# mbedXdotShield-V_1_0_1.net
KiCad netlist of a schematic drawn in EAGLE
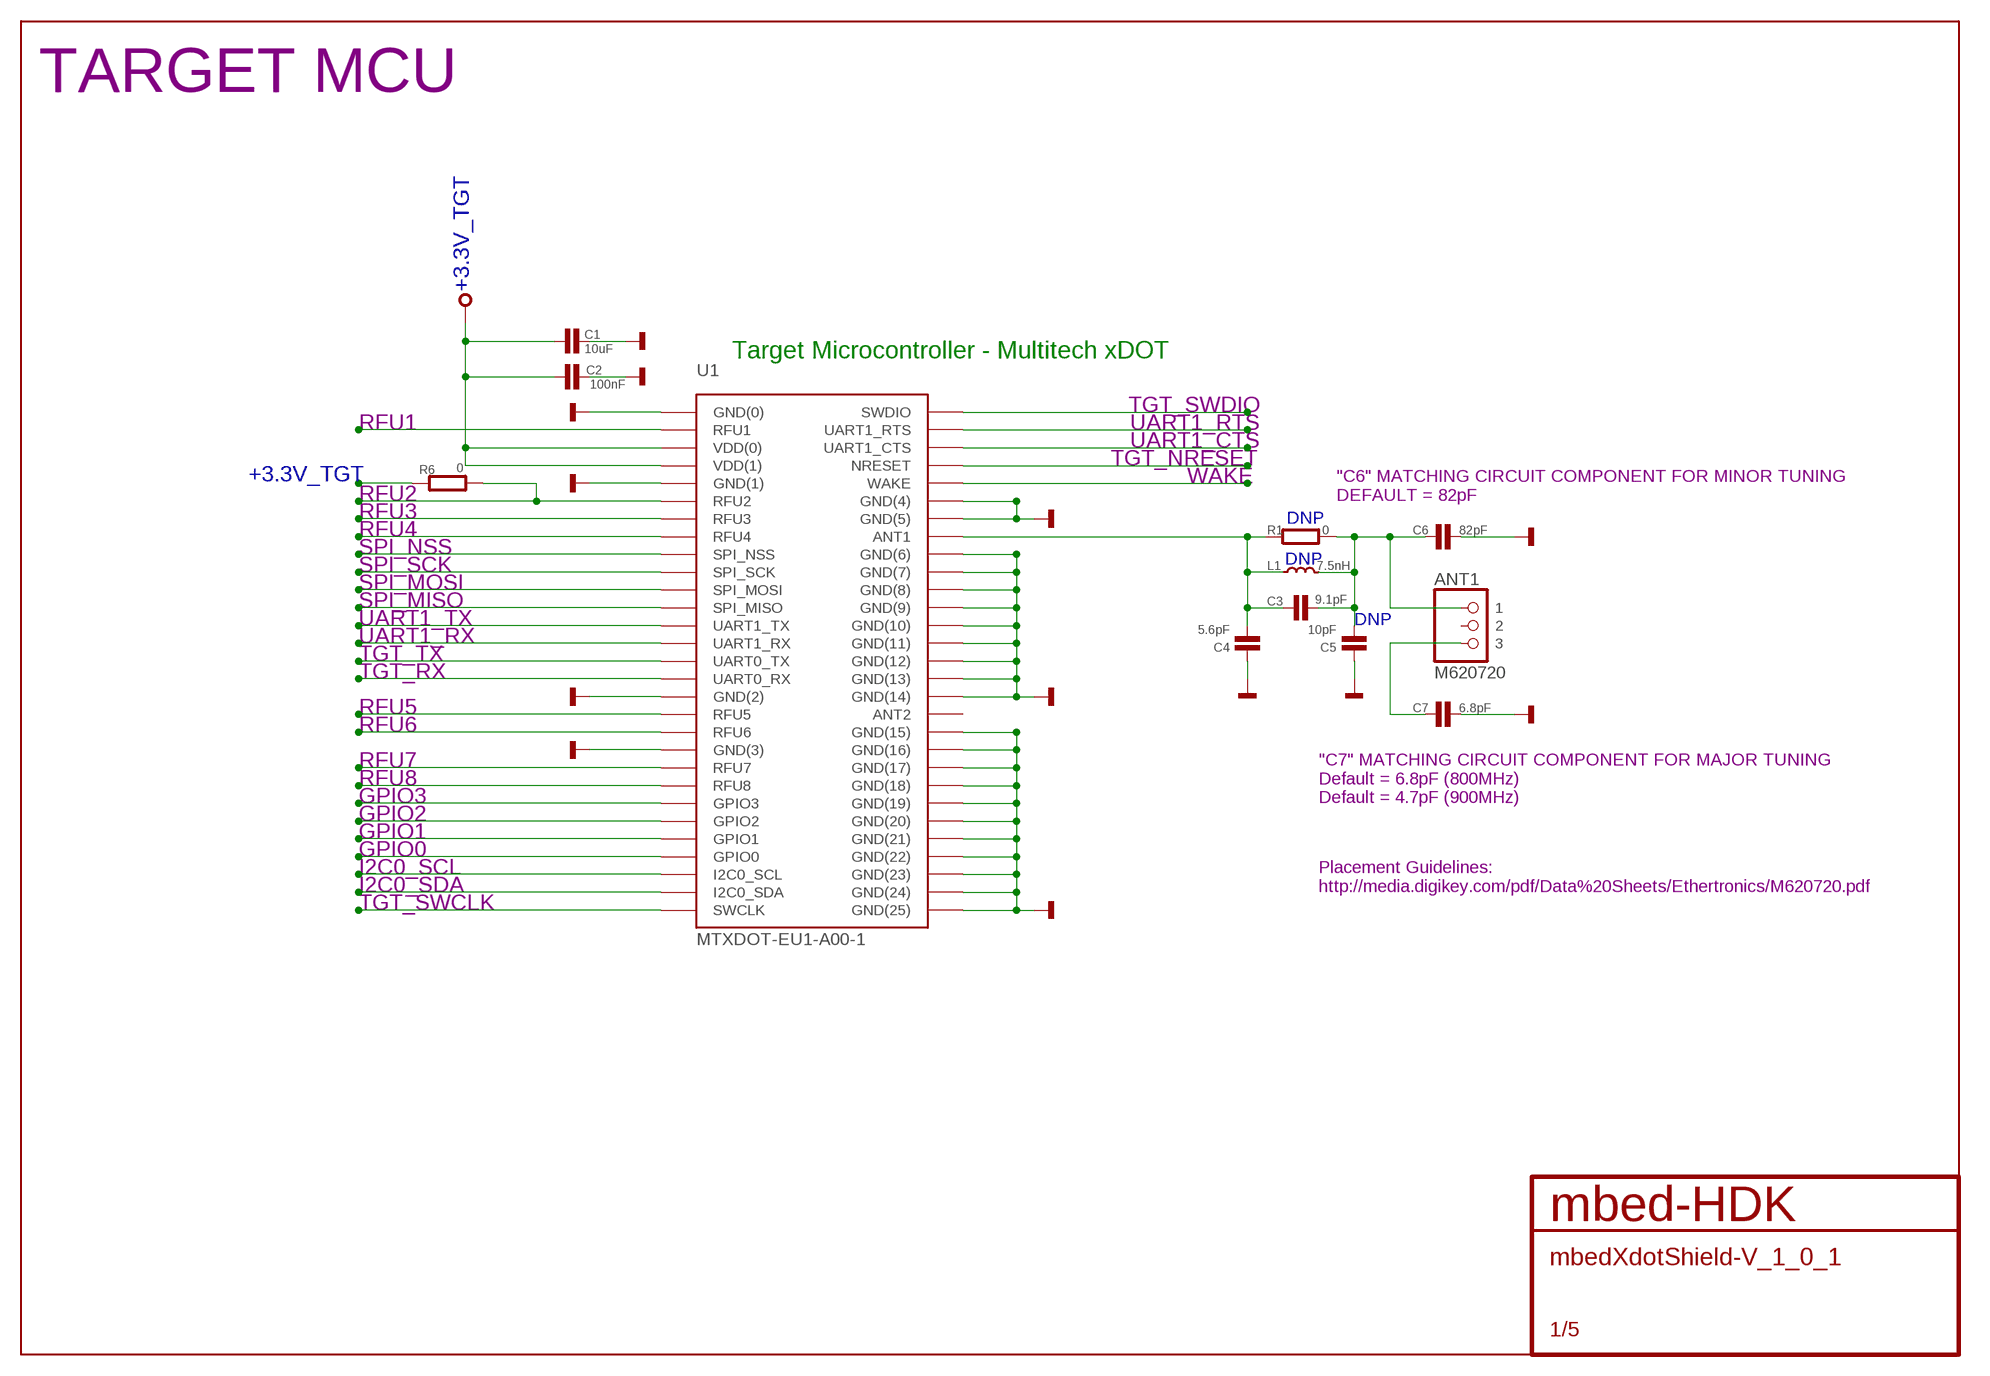
[diagram p0: schematic, sheet 1]
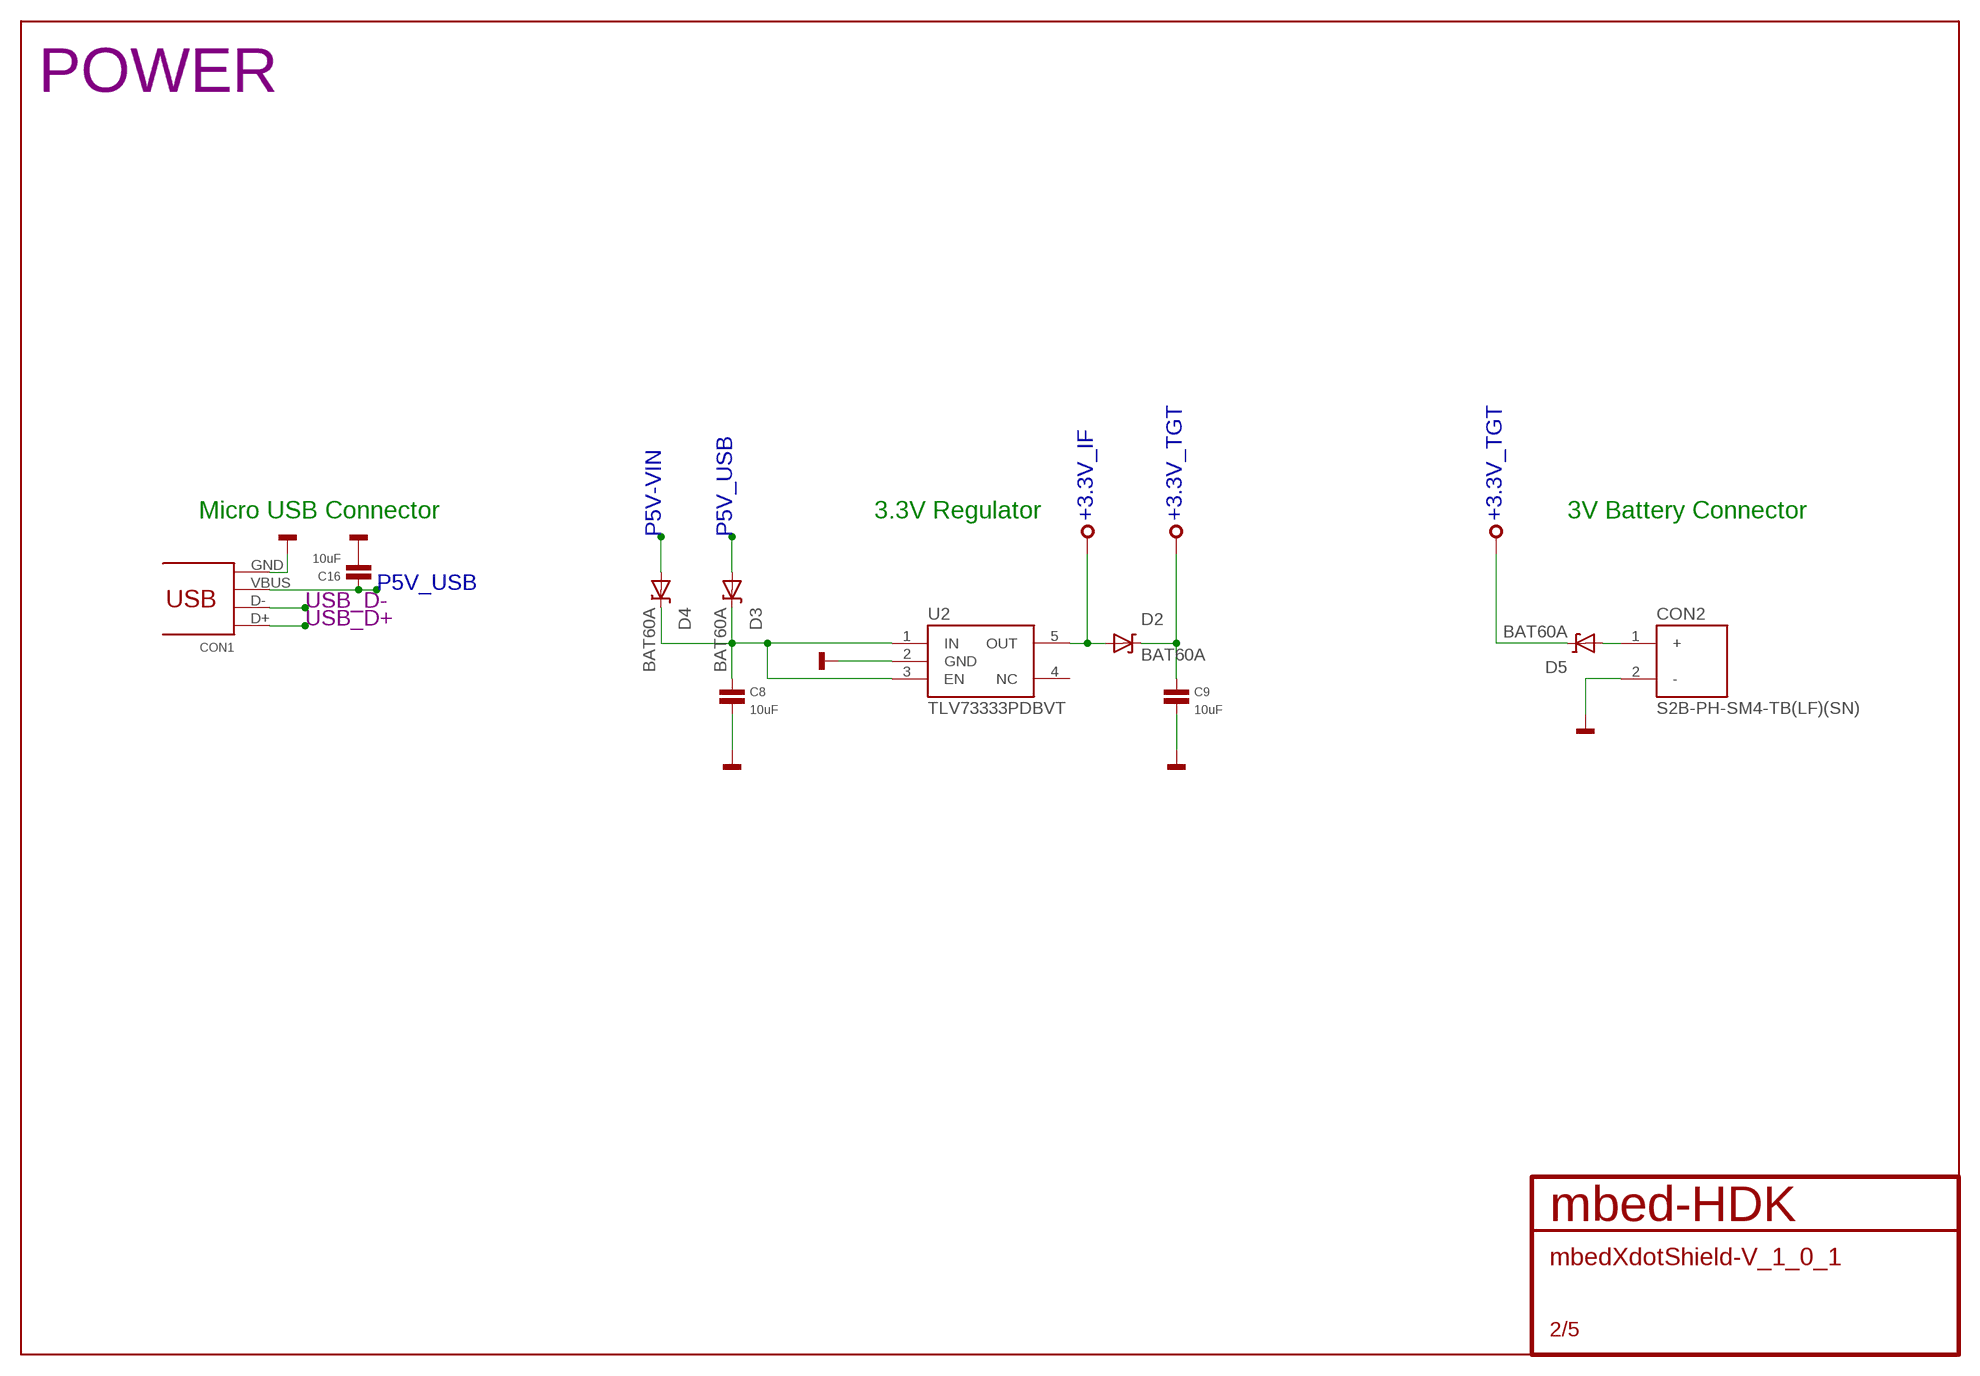
[diagram p1: schematic, sheet 2]
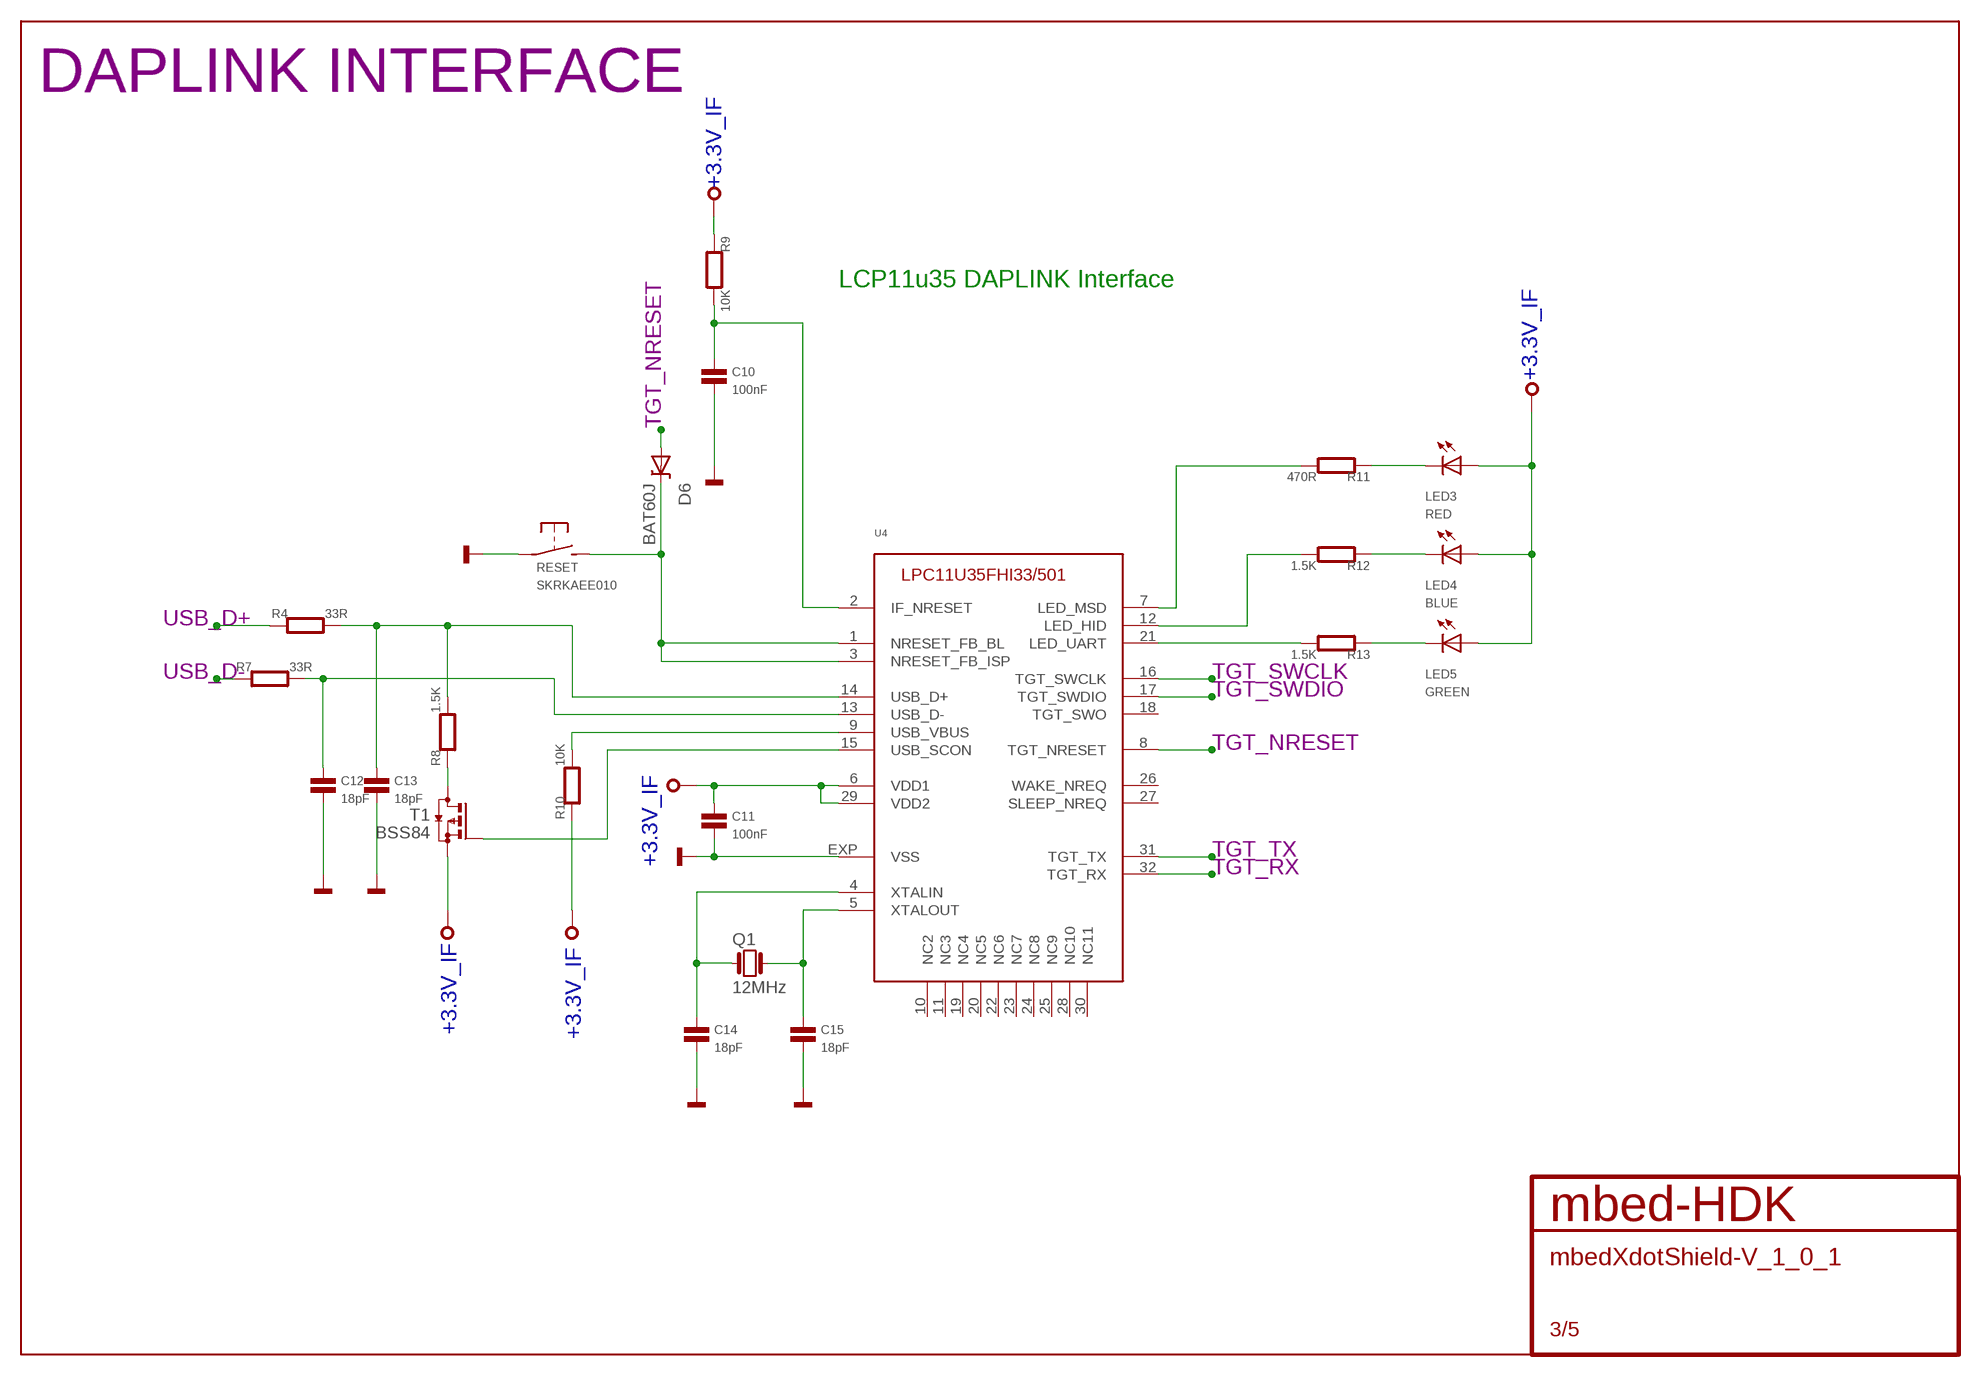
[diagram p2: schematic, sheet 3]
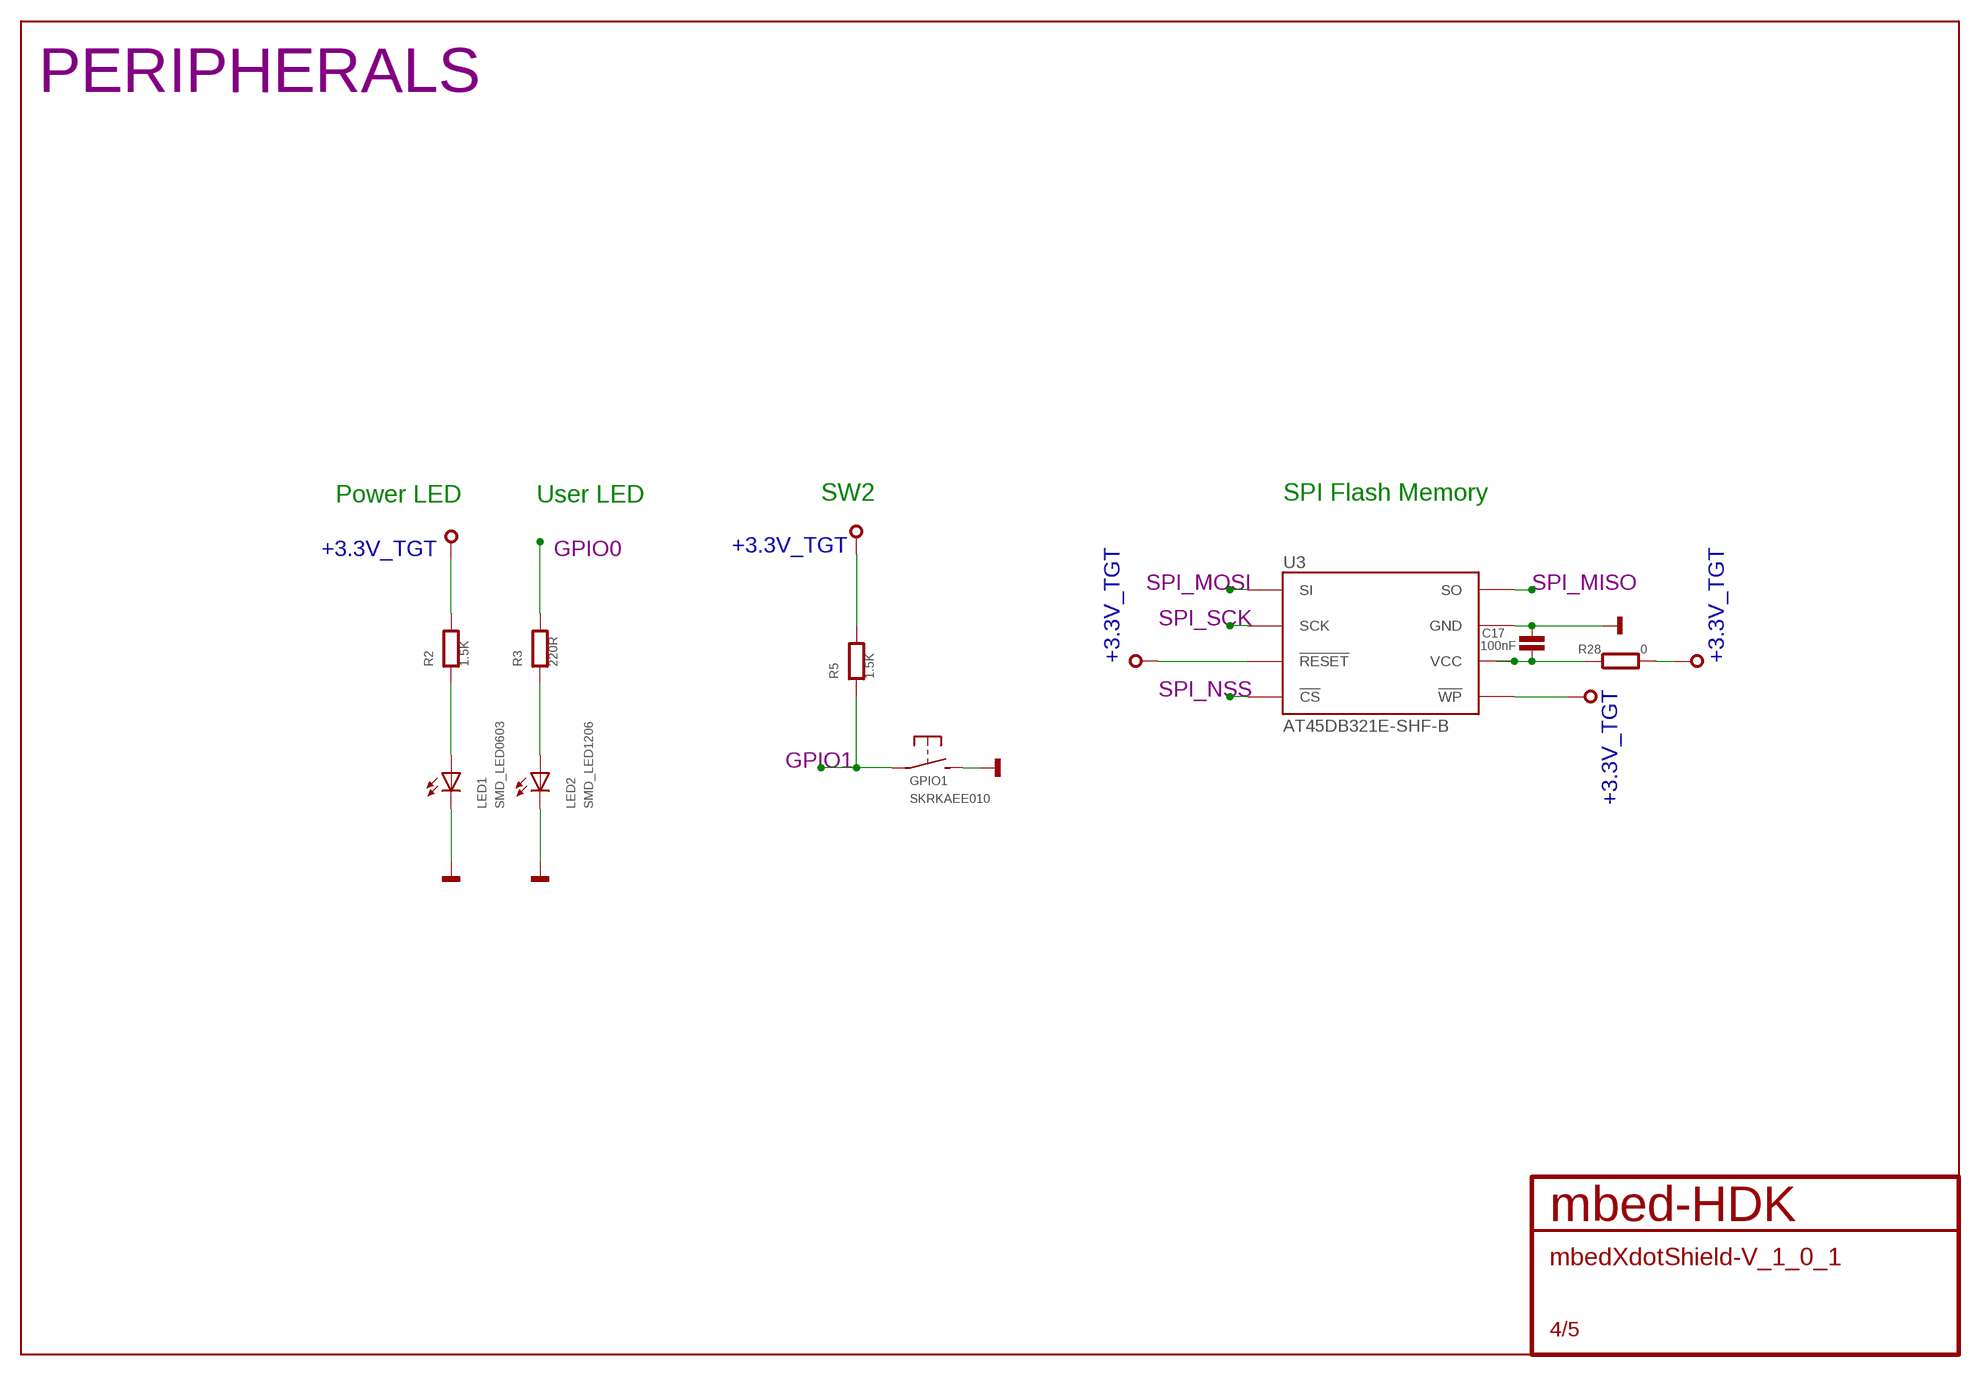
[diagram p3: schematic, sheet 4]
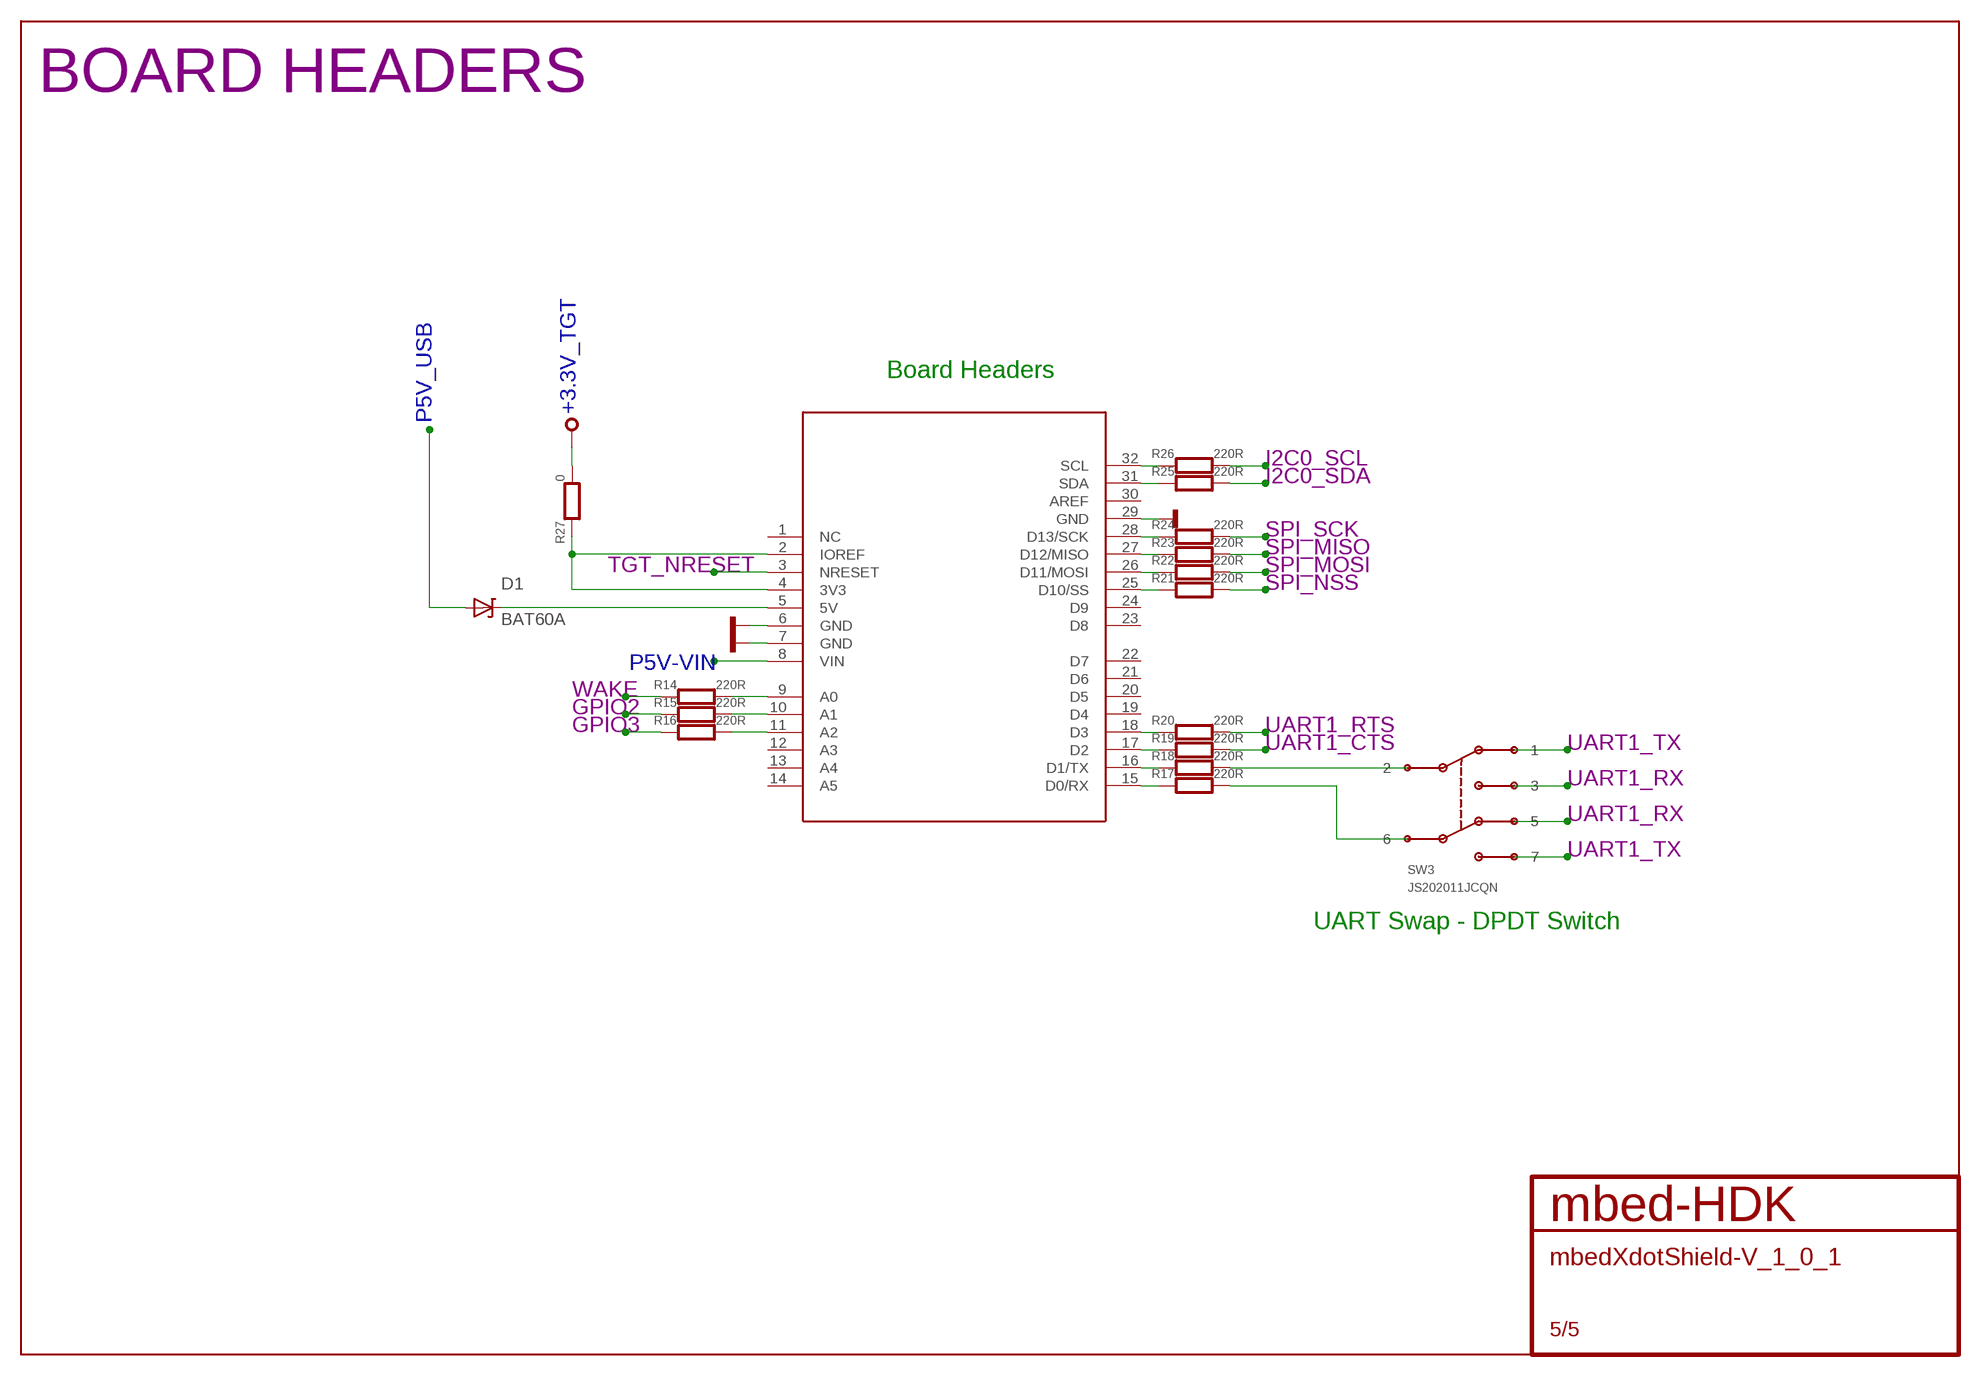
[diagram p4: schematic, sheet 5]

(export (version "E")
  (design (tool "Eeschema 10.0.6"))
  (components
    (comp (ref "C17")
      (value "100nF")
      (footprint "eagle-import:0603")
      (libsource (lib "eagle-import") (part "CAPACITOR0603"))
    )
    (comp (ref "GPIO1")
      (value "SKRKAEE010")
      (footprint "eagle-import:SKRKAEE010")
      (fields (field (name "MF") "ALPS"))
      (libsource (lib "eagle-import") (part "SKRKAEE010"))
    )
    (comp (ref "LED1")
      (value "SMD_LED0603")
      (footprint "eagle-import:CHIPLED_0603")
      (fields (field (name "MF") "Wurth Electronics Inc"))
      (libsource (lib "eagle-import") (part "SMD_LED0603"))
    )
    (comp (ref "LED2")
      (value "SMD_LED1206")
      (footprint "eagle-import:CHIPLED_1206")
      (fields (field (name "MF") "Wurth Electronics Inc"))
      (libsource (lib "eagle-import") (part "SMD_LED1206"))
    )
    (comp (ref "R2")
      (value "1.5K")
      (footprint "eagle-import:0402")
      (libsource (lib "eagle-import") (part "RESISTOR0402"))
    )
    (comp (ref "R3")
      (value "220R")
      (footprint "eagle-import:0402")
      (libsource (lib "eagle-import") (part "RESISTOR0402"))
    )
    (comp (ref "R5")
      (value "1.5K")
      (footprint "eagle-import:0402")
      (libsource (lib "eagle-import") (part "RESISTOR0402"))
    )
    (comp (ref "R28")
      (value "0")
      (footprint "eagle-import:0402")
      (libsource (lib "eagle-import") (part "RESISTOR0402"))
    )
    (comp (ref "U3")
      (value "AT45DB321E-SHF-B")
      (footprint "eagle-import:SO8")
      (fields (field (name "MF") "Adesto Technologies"))
      (libsource (lib "eagle-import") (part "AT45DB321E-SHF-B"))
    )
    (comp (ref "C10")
      (value "100nF")
      (footprint "eagle-import:0402")
      (libsource (lib "eagle-import") (part "CAPACITOR0402"))
    )
    (comp (ref "C11")
      (value "100nF")
      (footprint "eagle-import:0402")
      (libsource (lib "eagle-import") (part "CAPACITOR0402"))
    )
    (comp (ref "C12")
      (value "18pF")
      (footprint "eagle-import:0402")
      (libsource (lib "eagle-import") (part "CAPACITOR0402"))
    )
    (comp (ref "C13")
      (value "18pF")
      (footprint "eagle-import:0402")
      (libsource (lib "eagle-import") (part "CAPACITOR0402"))
    )
    (comp (ref "C14")
      (value "18pF")
      (footprint "eagle-import:0402")
      (libsource (lib "eagle-import") (part "CAPACITOR0402"))
    )
    (comp (ref "C15")
      (value "18pF")
      (footprint "eagle-import:0402")
      (libsource (lib "eagle-import") (part "CAPACITOR0402"))
    )
    (comp (ref "D6")
      (value "BAT60J")
      (footprint "eagle-import:SOD323")
      (fields (field (name "MF") "STMicroelectronics"))
      (libsource (lib "eagle-import") (part "BAT60J"))
    )
    (comp (ref "LED3")
      (value "RED")
      (footprint "eagle-import:CHIPLED_0603")
      (fields (field (name "MF") "Wurth Electronics Inc"))
      (libsource (lib "eagle-import") (part "SMD_LED0603"))
    )
    (comp (ref "LED4")
      (value "BLUE")
      (footprint "eagle-import:CHIPLED_0603")
      (fields (field (name "MF") "Wurth Electronics Inc"))
      (libsource (lib "eagle-import") (part "SMD_LED0603"))
    )
    (comp (ref "LED5")
      (value "GREEN")
      (footprint "eagle-import:CHIPLED_0603")
      (fields (field (name "MF") "Wurth Electronics Inc"))
      (libsource (lib "eagle-import") (part "SMD_LED0603"))
    )
    (comp (ref "Q1")
      (value "12MHz")
      (footprint "eagle-import:3.2X.2.5")
      (libsource (lib "eagle-import") (part "Q_3.2X2.5"))
    )
    (comp (ref "R4")
      (value "33R")
      (footprint "eagle-import:0402")
      (libsource (lib "eagle-import") (part "RESISTOR0402"))
    )
    (comp (ref "R7")
      (value "33R")
      (footprint "eagle-import:0402")
      (libsource (lib "eagle-import") (part "RESISTOR0402"))
    )
    (comp (ref "R8")
      (value "1.5K")
      (footprint "eagle-import:0402")
      (libsource (lib "eagle-import") (part "RESISTOR0402"))
    )
    (comp (ref "R9")
      (value "10K")
      (footprint "eagle-import:0402")
      (libsource (lib "eagle-import") (part "RESISTOR0402"))
    )
    (comp (ref "R10")
      (value "10K")
      (footprint "eagle-import:0402")
      (libsource (lib "eagle-import") (part "RESISTOR0402"))
    )
    (comp (ref "R11")
      (value "470R")
      (footprint "eagle-import:0402")
      (libsource (lib "eagle-import") (part "RESISTOR0402"))
    )
    (comp (ref "R12")
      (value "1.5K")
      (footprint "eagle-import:0402")
      (libsource (lib "eagle-import") (part "RESISTOR0402"))
    )
    (comp (ref "R13")
      (value "1.5K")
      (footprint "eagle-import:0402")
      (libsource (lib "eagle-import") (part "RESISTOR0402"))
    )
    (comp (ref "RESET")
      (value "SKRKAEE010")
      (footprint "eagle-import:SKRKAEE010")
      (fields (field (name "MF") "ALPS"))
      (libsource (lib "eagle-import") (part "SKRKAEE010"))
    )
    (comp (ref "T1")
      (value "BSS84")
      (footprint "eagle-import:SOT23-3")
      (fields (field (name "MF") "Fairchild Semiconductor"))
      (libsource (lib "eagle-import") (part "BSS84"))
    )
    (comp (ref "U4")
      (value "IF-LPC11U35")
      (footprint "eagle-import:HVQFN33")
      (libsource (lib "eagle-import") (part "IF-LPC11U35"))
    )
    (comp (ref "C8")
      (value "10uF")
      (footprint "eagle-import:0603")
      (libsource (lib "eagle-import") (part "CAPACITOR0603"))
    )
    (comp (ref "C9")
      (value "10uF")
      (footprint "eagle-import:0603")
      (libsource (lib "eagle-import") (part "CAPACITOR0603"))
    )
    (comp (ref "C16")
      (value "10uF")
      (footprint "eagle-import:0603")
      (libsource (lib "eagle-import") (part "CAPACITOR0603"))
    )
    (comp (ref "CON1")
      (value "47346-0001")
      (footprint "eagle-import:USB-MICRO-B-H")
      (fields (field (name "MF") "MOLEX"))
      (libsource (lib "eagle-import") (part "47346-0001"))
    )
    (comp (ref "CON2")
      (value "S2B-PH-SM4-TB(LF)(SN)")
      (footprint "eagle-import:S2B-PH-SM4-TB(LF)(SN)")
      (fields (field (name "MF") "JST"))
      (libsource (lib "eagle-import") (part "S2B-PH-SM4-TB(LF)(SN)"))
    )
    (comp (ref "D2")
      (value "BAT60A")
      (footprint "eagle-import:SOD323")
      (fields (field (name "MF") "Infineon"))
      (libsource (lib "eagle-import") (part "BAT60A"))
    )
    (comp (ref "D3")
      (value "BAT60A")
      (footprint "eagle-import:SOD323")
      (fields (field (name "MF") "Infineon"))
      (libsource (lib "eagle-import") (part "BAT60A"))
    )
    (comp (ref "D4")
      (value "BAT60A")
      (footprint "eagle-import:SOD323")
      (fields (field (name "MF") "Infineon"))
      (libsource (lib "eagle-import") (part "BAT60A"))
    )
    (comp (ref "D5")
      (value "BAT60A")
      (footprint "eagle-import:SOD323")
      (fields (field (name "MF") "Infineon"))
      (libsource (lib "eagle-import") (part "BAT60A"))
    )
    (comp (ref "U2")
      (value "TLV73333PDBVT")
      (footprint "eagle-import:SOT23-5")
      (fields (field (name "MF") "Texas Instruments"))
      (libsource (lib "eagle-import") (part "TLV73333PDBVT"))
    )
    (comp (ref "BRD1")
      (value "K64F/K22F-SHIELD")
      (footprint "eagle-import:K64F_K22F")
      (libsource (lib "eagle-import") (part "K64F/K22F-SHIELD"))
    )
    (comp (ref "D1")
      (value "BAT60A")
      (footprint "eagle-import:SOD323")
      (fields (field (name "MF") "Infineon"))
      (libsource (lib "eagle-import") (part "BAT60A"))
    )
    (comp (ref "R14")
      (value "220R")
      (footprint "eagle-import:0402")
      (libsource (lib "eagle-import") (part "RESISTOR0402"))
    )
    (comp (ref "R15")
      (value "220R")
      (footprint "eagle-import:0402")
      (libsource (lib "eagle-import") (part "RESISTOR0402"))
    )
    (comp (ref "R16")
      (value "220R")
      (footprint "eagle-import:0402")
      (libsource (lib "eagle-import") (part "RESISTOR0402"))
    )
    (comp (ref "R17")
      (value "220R")
      (footprint "eagle-import:0402")
      (libsource (lib "eagle-import") (part "RESISTOR0402"))
    )
    (comp (ref "R18")
      (value "220R")
      (footprint "eagle-import:0402")
      (libsource (lib "eagle-import") (part "RESISTOR0402"))
    )
    (comp (ref "R19")
      (value "220R")
      (footprint "eagle-import:0402")
      (libsource (lib "eagle-import") (part "RESISTOR0402"))
    )
    (comp (ref "R20")
      (value "220R")
      (footprint "eagle-import:0402")
      (libsource (lib "eagle-import") (part "RESISTOR0402"))
    )
    (comp (ref "R21")
      (value "220R")
      (footprint "eagle-import:0402")
      (libsource (lib "eagle-import") (part "RESISTOR0402"))
    )
    (comp (ref "R22")
      (value "220R")
      (footprint "eagle-import:0402")
      (libsource (lib "eagle-import") (part "RESISTOR0402"))
    )
    (comp (ref "R23")
      (value "220R")
      (footprint "eagle-import:0402")
      (libsource (lib "eagle-import") (part "RESISTOR0402"))
    )
    (comp (ref "R24")
      (value "220R")
      (footprint "eagle-import:0402")
      (libsource (lib "eagle-import") (part "RESISTOR0402"))
    )
    (comp (ref "R25")
      (value "220R")
      (footprint "eagle-import:0402")
      (libsource (lib "eagle-import") (part "RESISTOR0402"))
    )
    (comp (ref "R26")
      (value "220R")
      (footprint "eagle-import:0402")
      (libsource (lib "eagle-import") (part "RESISTOR0402"))
    )
    (comp (ref "R27")
      (value "0")
      (footprint "eagle-import:0402")
      (libsource (lib "eagle-import") (part "RESISTOR0402"))
    )
    (comp (ref "SW3")
      (value "JS202011JCQN")
      (footprint "eagle-import:JS202011JCQN")
      (fields (field (name "MF") "C&K Components"))
      (libsource (lib "eagle-import") (part "JS202011JCQN"))
    )
    (comp (ref "ANT1")
      (value "M620720")
      (footprint "eagle-import:M620720")
      (fields (field (name "MF") "Ethertronics"))
      (libsource (lib "eagle-import") (part "M620720"))
    )
    (comp (ref "C1")
      (value "10uF")
      (footprint "eagle-import:0603")
      (libsource (lib "eagle-import") (part "CAPACITOR0603"))
    )
    (comp (ref "C2")
      (value "100nF")
      (footprint "eagle-import:0603")
      (libsource (lib "eagle-import") (part "CAPACITOR0603"))
    )
    (comp (ref "C3")
      (value "9.1pF")
      (footprint "eagle-import:0402")
      (libsource (lib "eagle-import") (part "CAPACITOR0402"))
    )
    (comp (ref "C4")
      (value "5.6pF")
      (footprint "eagle-import:0402")
      (libsource (lib "eagle-import") (part "CAPACITOR0402"))
    )
    (comp (ref "C5")
      (value "10pF")
      (footprint "eagle-import:0402")
      (libsource (lib "eagle-import") (part "CAPACITOR0402"))
    )
    (comp (ref "C6")
      (value "82pF")
      (footprint "eagle-import:0402")
      (libsource (lib "eagle-import") (part "CAPACITOR0402"))
    )
    (comp (ref "C7")
      (value "6.8pF")
      (footprint "eagle-import:0402")
      (libsource (lib "eagle-import") (part "CAPACITOR0402"))
    )
    (comp (ref "L1")
      (value "7.5nH")
      (footprint "eagle-import:0402")
      (libsource (lib "eagle-import") (part "INDUCTOR0402"))
    )
    (comp (ref "R1")
      (value "0")
      (footprint "eagle-import:0402")
      (libsource (lib "eagle-import") (part "RESISTOR0402"))
    )
    (comp (ref "R6")
      (value "0")
      (footprint "eagle-import:0402")
      (libsource (lib "eagle-import") (part "RESISTOR0402"))
    )
    (comp (ref "U1")
      (value "MTXDOT-EU1-A00-1")
      (footprint "eagle-import:MTXDOT-EU1_NA1-A00-1")
      (fields (field (name "MF") "Multi-Tech Systems Inc."))
      (libsource (lib "eagle-import") (part "MTXDOT-EU1-A00-1"))
    )
  )
  (nets
    (net (code "1") (name "+3.3V_IF") (class "Default")
      (node (ref "C11") (pin "1") (pinfunction "P$1_1") (pintype "passive"))
      (node (ref "D2") (pin "A") (pinfunction "A_A") (pintype "passive"))
      (node (ref "LED3") (pin "A") (pinfunction "A_A") (pintype "passive"))
      (node (ref "LED4") (pin "A") (pinfunction "A_A") (pintype "passive"))
      (node (ref "LED5") (pin "A") (pinfunction "A_A") (pintype "passive"))
      (node (ref "R10") (pin "1") (pinfunction "P$1_1") (pintype "passive"))
      (node (ref "R9") (pin "1") (pinfunction "P$1_1") (pintype "passive"))
      (node (ref "T1") (pin "2") (pinfunction "S_2") (pintype "passive"))
      (node (ref "U2") (pin "5") (pinfunction "OUT_5") (pintype "bidirectional"))
      (node (ref "U4") (pin "29") (pinfunction "VDD2_29") (pintype "bidirectional"))
      (node (ref "U4") (pin "6") (pinfunction "VDD1_6") (pintype "bidirectional"))
    )
    (net (code "2") (name "+3.3V_TGT") (class "Default")
      (node (ref "C1") (pin "1") (pinfunction "P$1_1") (pintype "passive"))
      (node (ref "C2") (pin "1") (pinfunction "P$1_1") (pintype "passive"))
      (node (ref "C9") (pin "1") (pinfunction "P$1_1") (pintype "passive"))
      (node (ref "D2") (pin "K") (pinfunction "K_K") (pintype "passive"))
      (node (ref "D5") (pin "K") (pinfunction "K_K") (pintype "passive"))
      (node (ref "R2") (pin "2") (pinfunction "P$2_2") (pintype "passive"))
      (node (ref "R27") (pin "2") (pinfunction "P$2_2") (pintype "passive"))
      (node (ref "R28") (pin "2") (pinfunction "P$2_2") (pintype "passive"))
      (node (ref "R5") (pin "2") (pinfunction "P$2_2") (pintype "passive"))
      (node (ref "R6") (pin "1") (pinfunction "P$1_1") (pintype "passive"))
      (node (ref "U1") (pin "P$3") (pinfunction "VDD(0)_P$3") (pintype "bidirectional"))
      (node (ref "U1") (pin "P$4") (pinfunction "VDD(1)_P$4") (pintype "bidirectional"))
      (node (ref "U3") (pin "3") (pinfunction "~{RESET}_3") (pintype "bidirectional"))
      (node (ref "U3") (pin "5") (pinfunction "~{WP}_5") (pintype "bidirectional"))
    )
    (net (code "3") (name "GND") (class "Default")
      (node (ref "BRD1") (pin "29") (pinfunction "GND_29") (pintype "bidirectional"))
      (node (ref "BRD1") (pin "6") (pinfunction "GND_6") (pintype "bidirectional"))
      (node (ref "BRD1") (pin "7") (pinfunction "GND_7") (pintype "bidirectional"))
      (node (ref "C1") (pin "2") (pinfunction "P$2_2") (pintype "passive"))
      (node (ref "C10") (pin "2") (pinfunction "P$2_2") (pintype "passive"))
      (node (ref "C11") (pin "2") (pinfunction "P$2_2") (pintype "passive"))
      (node (ref "C12") (pin "2") (pinfunction "P$2_2") (pintype "passive"))
      (node (ref "C13") (pin "2") (pinfunction "P$2_2") (pintype "passive"))
      (node (ref "C14") (pin "2") (pinfunction "P$2_2") (pintype "passive"))
      (node (ref "C15") (pin "2") (pinfunction "P$2_2") (pintype "passive"))
      (node (ref "C16") (pin "2") (pinfunction "P$2_2") (pintype "passive"))
      (node (ref "C17") (pin "1") (pinfunction "P$1_1") (pintype "passive"))
      (node (ref "C2") (pin "2") (pinfunction "P$2_2") (pintype "passive"))
      (node (ref "C4") (pin "1") (pinfunction "P$1_1") (pintype "passive"))
      (node (ref "C5") (pin "1") (pinfunction "P$1_1") (pintype "passive"))
      (node (ref "C6") (pin "1") (pinfunction "P$1_1") (pintype "passive"))
      (node (ref "C7") (pin "1") (pinfunction "P$1_1") (pintype "passive"))
      (node (ref "C8") (pin "2") (pinfunction "P$2_2") (pintype "passive"))
      (node (ref "C9") (pin "2") (pinfunction "P$2_2") (pintype "passive"))
      (node (ref "CON1") (pin "GND") (pinfunction "GND_GND") (pintype "bidirectional"))
      (node (ref "CON2") (pin "2") (pinfunction "-_2") (pintype "bidirectional"))
      (node (ref "GPIO1") (pin "P$2") (pinfunction "S_P$2") (pintype "passive"))
      (node (ref "LED1") (pin "C") (pinfunction "C_C") (pintype "passive"))
      (node (ref "LED2") (pin "C") (pinfunction "C_C") (pintype "passive"))
      (node (ref "RESET") (pin "P$1") (pinfunction "P_P$1") (pintype "passive"))
      (node (ref "U1") (pin "P$1") (pinfunction "GND(0)_P$1") (pintype "bidirectional"))
      (node (ref "U1") (pin "P$17") (pinfunction "GND(2)_P$17") (pintype "bidirectional"))
      (node (ref "U1") (pin "P$20") (pinfunction "GND(3)_P$20") (pintype "bidirectional"))
      (node (ref "U1") (pin "P$35") (pinfunction "GND(4)_P$35") (pintype "bidirectional"))
      (node (ref "U1") (pin "P$36") (pinfunction "GND(5)_P$36") (pintype "bidirectional"))
      (node (ref "U1") (pin "P$38") (pinfunction "GND(6)_P$38") (pintype "bidirectional"))
      (node (ref "U1") (pin "P$39") (pinfunction "GND(7)_P$39") (pintype "bidirectional"))
      (node (ref "U1") (pin "P$40") (pinfunction "GND(8)_P$40") (pintype "bidirectional"))
      (node (ref "U1") (pin "P$41") (pinfunction "GND(9)_P$41") (pintype "bidirectional"))
      (node (ref "U1") (pin "P$42") (pinfunction "GND(10)_P$42") (pintype "bidirectional"))
      (node (ref "U1") (pin "P$43") (pinfunction "GND(11)_P$43") (pintype "bidirectional"))
      (node (ref "U1") (pin "P$44") (pinfunction "GND(12)_P$44") (pintype "bidirectional"))
      (node (ref "U1") (pin "P$45") (pinfunction "GND(13)_P$45") (pintype "bidirectional"))
      (node (ref "U1") (pin "P$46") (pinfunction "GND(14)_P$46") (pintype "bidirectional"))
      (node (ref "U1") (pin "P$48") (pinfunction "GND(15)_P$48") (pintype "bidirectional"))
      (node (ref "U1") (pin "P$49") (pinfunction "GND(16)_P$49") (pintype "bidirectional"))
      (node (ref "U1") (pin "P$5") (pinfunction "GND(1)_P$5") (pintype "bidirectional"))
      (node (ref "U1") (pin "P$50") (pinfunction "GND(17)_P$50") (pintype "bidirectional"))
      (node (ref "U1") (pin "P$51") (pinfunction "GND(18)_P$51") (pintype "bidirectional"))
      (node (ref "U1") (pin "P$52") (pinfunction "GND(19)_P$52") (pintype "bidirectional"))
      (node (ref "U1") (pin "P$53") (pinfunction "GND(20)_P$53") (pintype "bidirectional"))
      (node (ref "U1") (pin "P$54") (pinfunction "GND(21)_P$54") (pintype "bidirectional"))
      (node (ref "U1") (pin "P$55") (pinfunction "GND(22)_P$55") (pintype "bidirectional"))
      (node (ref "U1") (pin "P$56") (pinfunction "GND(23)_P$56") (pintype "bidirectional"))
      (node (ref "U1") (pin "P$57") (pinfunction "GND(24)_P$57") (pintype "bidirectional"))
      (node (ref "U1") (pin "P$58") (pinfunction "GND(25)_P$58") (pintype "bidirectional"))
      (node (ref "U2") (pin "2") (pinfunction "GND_2") (pintype "bidirectional"))
      (node (ref "U3") (pin "7") (pinfunction "GND_7") (pintype "bidirectional"))
      (node (ref "U4") (pin "EXP") (pinfunction "VSS_EXP") (pintype "bidirectional"))
    )
    (net (code "4") (name "GPIO0") (class "Default")
      (node (ref "R3") (pin "2") (pinfunction "P$2_2") (pintype "passive"))
      (node (ref "U1") (pin "P$26") (pinfunction "GPIO0_P$26") (pintype "bidirectional"))
    )
    (net (code "5") (name "GPIO1") (class "Default")
      (node (ref "GPIO1") (pin "P$1") (pinfunction "P_P$1") (pintype "passive"))
      (node (ref "R5") (pin "1") (pinfunction "P$1_1") (pintype "passive"))
      (node (ref "U1") (pin "P$25") (pinfunction "GPIO1_P$25") (pintype "bidirectional"))
    )
    (net (code "6") (name "GPIO2") (class "Default")
      (node (ref "R15") (pin "1") (pinfunction "P$1_1") (pintype "passive"))
      (node (ref "U1") (pin "P$24") (pinfunction "GPIO2_P$24") (pintype "bidirectional"))
    )
    (net (code "7") (name "GPIO3") (class "Default")
      (node (ref "R16") (pin "1") (pinfunction "P$1_1") (pintype "passive"))
      (node (ref "U1") (pin "P$23") (pinfunction "GPIO3_P$23") (pintype "bidirectional"))
    )
    (net (code "8") (name "I2C0_SCL") (class "Default")
      (node (ref "R26") (pin "2") (pinfunction "P$2_2") (pintype "passive"))
      (node (ref "U1") (pin "P$27") (pinfunction "I2C0_SCL_P$27") (pintype "bidirectional"))
    )
    (net (code "9") (name "I2C0_SDA") (class "Default")
      (node (ref "R25") (pin "2") (pinfunction "P$2_2") (pintype "passive"))
      (node (ref "U1") (pin "P$28") (pinfunction "I2C0_SDA_P$28") (pintype "bidirectional"))
    )
    (net (code "10") (name "Net-(ANT1-1)") (class "Default")
      (node (ref "ANT1") (pin "P$1") (pinfunction "1_P$1") (pintype "passive"))
      (node (ref "C3") (pin "2") (pinfunction "P$2_2") (pintype "passive"))
      (node (ref "C5") (pin "2") (pinfunction "P$2_2") (pintype "passive"))
      (node (ref "C6") (pin "2") (pinfunction "P$2_2") (pintype "passive"))
      (node (ref "L1") (pin "2") (pinfunction "P$2_2") (pintype "bidirectional"))
      (node (ref "R1") (pin "2") (pinfunction "P$2_2") (pintype "passive"))
    )
    (net (code "11") (name "Net-(ANT1-3)") (class "Default")
      (node (ref "ANT1") (pin "P$3") (pinfunction "3_P$3") (pintype "passive"))
      (node (ref "C7") (pin "2") (pinfunction "P$2_2") (pintype "passive"))
    )
    (net (code "12") (name "Net-(BRD1-3V3)") (class "Default")
      (node (ref "BRD1") (pin "2") (pinfunction "IOREF_2") (pintype "bidirectional"))
      (node (ref "BRD1") (pin "4") (pinfunction "3V3_4") (pintype "bidirectional"))
      (node (ref "R27") (pin "1") (pinfunction "P$1_1") (pintype "passive"))
    )
    (net (code "13") (name "Net-(BRD1-5V)") (class "Default")
      (node (ref "BRD1") (pin "5") (pinfunction "5V_5") (pintype "bidirectional"))
      (node (ref "D1") (pin "K") (pinfunction "K_K") (pintype "passive"))
    )
    (net (code "14") (name "Net-(BRD1-A0)") (class "Default")
      (node (ref "BRD1") (pin "9") (pinfunction "A0_9") (pintype "bidirectional"))
      (node (ref "R14") (pin "2") (pinfunction "P$2_2") (pintype "passive"))
    )
    (net (code "15") (name "Net-(BRD1-A1)") (class "Default")
      (node (ref "BRD1") (pin "10") (pinfunction "A1_10") (pintype "bidirectional"))
      (node (ref "R15") (pin "2") (pinfunction "P$2_2") (pintype "passive"))
    )
    (net (code "16") (name "Net-(BRD1-A2)") (class "Default")
      (node (ref "BRD1") (pin "11") (pinfunction "A2_11") (pintype "bidirectional"))
      (node (ref "R16") (pin "2") (pinfunction "P$2_2") (pintype "passive"))
    )
    (net (code "17") (name "Net-(BRD1-D0{slash}RX)") (class "Default")
      (node (ref "BRD1") (pin "15") (pinfunction "D0/RX_15") (pintype "bidirectional"))
      (node (ref "R17") (pin "1") (pinfunction "P$1_1") (pintype "passive"))
    )
    (net (code "18") (name "Net-(BRD1-D1{slash}TX)") (class "Default")
      (node (ref "BRD1") (pin "16") (pinfunction "D1/TX_16") (pintype "bidirectional"))
      (node (ref "R18") (pin "1") (pinfunction "P$1_1") (pintype "passive"))
    )
    (net (code "19") (name "Net-(BRD1-D2)") (class "Default")
      (node (ref "BRD1") (pin "17") (pinfunction "D2_17") (pintype "bidirectional"))
      (node (ref "R19") (pin "1") (pinfunction "P$1_1") (pintype "passive"))
    )
    (net (code "20") (name "Net-(BRD1-D3)") (class "Default")
      (node (ref "BRD1") (pin "18") (pinfunction "D3_18") (pintype "bidirectional"))
      (node (ref "R20") (pin "1") (pinfunction "P$1_1") (pintype "passive"))
    )
    (net (code "21") (name "Net-(BRD1-D10{slash}SS)") (class "Default")
      (node (ref "BRD1") (pin "25") (pinfunction "D10/SS_25") (pintype "bidirectional"))
      (node (ref "R21") (pin "1") (pinfunction "P$1_1") (pintype "passive"))
    )
    (net (code "22") (name "Net-(BRD1-D11{slash}MOSI)") (class "Default")
      (node (ref "BRD1") (pin "26") (pinfunction "D11/MOSI_26") (pintype "bidirectional"))
      (node (ref "R22") (pin "1") (pinfunction "P$1_1") (pintype "passive"))
    )
    (net (code "23") (name "Net-(BRD1-D12{slash}MISO)") (class "Default")
      (node (ref "BRD1") (pin "27") (pinfunction "D12/MISO_27") (pintype "bidirectional"))
      (node (ref "R23") (pin "1") (pinfunction "P$1_1") (pintype "passive"))
    )
    (net (code "24") (name "Net-(BRD1-D13{slash}SCK)") (class "Default")
      (node (ref "BRD1") (pin "28") (pinfunction "D13/SCK_28") (pintype "bidirectional"))
      (node (ref "R24") (pin "1") (pinfunction "P$1_1") (pintype "passive"))
    )
    (net (code "25") (name "Net-(BRD1-SCL)") (class "Default")
      (node (ref "BRD1") (pin "32") (pinfunction "SCL_32") (pintype "bidirectional"))
      (node (ref "R26") (pin "1") (pinfunction "P$1_1") (pintype "passive"))
    )
    (net (code "26") (name "Net-(BRD1-SDA)") (class "Default")
      (node (ref "BRD1") (pin "31") (pinfunction "SDA_31") (pintype "bidirectional"))
      (node (ref "R25") (pin "1") (pinfunction "P$1_1") (pintype "passive"))
    )
    (net (code "27") (name "Net-(C3-P$1)") (class "Default")
      (node (ref "C3") (pin "1") (pinfunction "P$1_1") (pintype "passive"))
      (node (ref "C4") (pin "2") (pinfunction "P$2_2") (pintype "passive"))
      (node (ref "L1") (pin "1") (pinfunction "P$1_1") (pintype "bidirectional"))
      (node (ref "R1") (pin "1") (pinfunction "P$1_1") (pintype "passive"))
      (node (ref "U1") (pin "P$37") (pinfunction "ANT1_P$37") (pintype "bidirectional"))
    )
    (net (code "28") (name "Net-(C8-P$1)") (class "Default")
      (node (ref "C8") (pin "1") (pinfunction "P$1_1") (pintype "passive"))
      (node (ref "D3") (pin "K") (pinfunction "K_K") (pintype "passive"))
      (node (ref "D4") (pin "K") (pinfunction "K_K") (pintype "passive"))
      (node (ref "U2") (pin "1") (pinfunction "IN_1") (pintype "bidirectional"))
      (node (ref "U2") (pin "3") (pinfunction "EN_3") (pintype "bidirectional"))
    )
    (net (code "29") (name "Net-(C10-P$1)") (class "Default")
      (node (ref "C10") (pin "1") (pinfunction "P$1_1") (pintype "passive"))
      (node (ref "R9") (pin "2") (pinfunction "P$2_2") (pintype "passive"))
      (node (ref "U4") (pin "2") (pinfunction "IF_NRESET_2") (pintype "bidirectional"))
    )
    (net (code "30") (name "Net-(C12-P$1)") (class "Default")
      (node (ref "C12") (pin "1") (pinfunction "P$1_1") (pintype "passive"))
      (node (ref "R7") (pin "2") (pinfunction "P$2_2") (pintype "passive"))
      (node (ref "U4") (pin "13") (pinfunction "USB_D-_13") (pintype "bidirectional"))
    )
    (net (code "31") (name "Net-(C13-P$1)") (class "Default")
      (node (ref "C13") (pin "1") (pinfunction "P$1_1") (pintype "passive"))
      (node (ref "R4") (pin "2") (pinfunction "P$2_2") (pintype "passive"))
      (node (ref "R8") (pin "2") (pinfunction "P$2_2") (pintype "passive"))
      (node (ref "U4") (pin "14") (pinfunction "USB_D+_14") (pintype "bidirectional"))
    )
    (net (code "32") (name "Net-(C14-P$1)") (class "Default")
      (node (ref "C14") (pin "1") (pinfunction "P$1_1") (pintype "passive"))
      (node (ref "Q1") (pin "P$1") (pinfunction "1_P$1") (pintype "passive"))
      (node (ref "U4") (pin "4") (pinfunction "XTALIN_4") (pintype "bidirectional"))
    )
    (net (code "33") (name "Net-(C15-P$1)") (class "Default")
      (node (ref "C15") (pin "1") (pinfunction "P$1_1") (pintype "passive"))
      (node (ref "Q1") (pin "P$3") (pinfunction "2_P$3") (pintype "passive"))
      (node (ref "U4") (pin "5") (pinfunction "XTALOUT_5") (pintype "bidirectional"))
    )
    (net (code "34") (name "Net-(C17-P$2)") (class "Default")
      (node (ref "C17") (pin "2") (pinfunction "P$2_2") (pintype "passive"))
      (node (ref "R28") (pin "1") (pinfunction "P$1_1") (pintype "passive"))
      (node (ref "U3") (pin "6") (pinfunction "VCC_6") (pintype "bidirectional"))
    )
    (net (code "35") (name "Net-(CON2-+)") (class "Default")
      (node (ref "CON2") (pin "1") (pinfunction "+_1") (pintype "bidirectional"))
      (node (ref "D5") (pin "A") (pinfunction "A_A") (pintype "passive"))
    )
    (net (code "36") (name "Net-(R2-P$1)") (class "Default")
      (node (ref "LED1") (pin "A") (pinfunction "A_A") (pintype "passive"))
      (node (ref "R2") (pin "1") (pinfunction "P$1_1") (pintype "passive"))
    )
    (net (code "37") (name "Net-(R3-P$1)") (class "Default")
      (node (ref "LED2") (pin "A") (pinfunction "A_A") (pintype "passive"))
      (node (ref "R3") (pin "1") (pinfunction "P$1_1") (pintype "passive"))
    )
    (net (code "38") (name "Net-(R8-P$1)") (class "Default")
      (node (ref "R8") (pin "1") (pinfunction "P$1_1") (pintype "passive"))
      (node (ref "T1") (pin "3") (pinfunction "D_3") (pintype "passive"))
    )
    (net (code "39") (name "Net-(R10-P$2)") (class "Default")
      (node (ref "R10") (pin "2") (pinfunction "P$2_2") (pintype "passive"))
      (node (ref "U4") (pin "9") (pinfunction "USB_VBUS_9") (pintype "bidirectional"))
    )
    (net (code "40") (name "Net-(R11-P$1)") (class "Default")
      (node (ref "LED3") (pin "C") (pinfunction "C_C") (pintype "passive"))
      (node (ref "R11") (pin "1") (pinfunction "P$1_1") (pintype "passive"))
    )
    (net (code "41") (name "Net-(R11-P$2)") (class "Default")
      (node (ref "R11") (pin "2") (pinfunction "P$2_2") (pintype "passive"))
      (node (ref "U4") (pin "7") (pinfunction "LED_MSD_7") (pintype "bidirectional"))
    )
    (net (code "42") (name "Net-(R12-P$1)") (class "Default")
      (node (ref "LED4") (pin "C") (pinfunction "C_C") (pintype "passive"))
      (node (ref "R12") (pin "1") (pinfunction "P$1_1") (pintype "passive"))
    )
    (net (code "43") (name "Net-(R12-P$2)") (class "Default")
      (node (ref "R12") (pin "2") (pinfunction "P$2_2") (pintype "passive"))
      (node (ref "U4") (pin "12") (pinfunction "LED_HID_12") (pintype "bidirectional"))
    )
    (net (code "44") (name "Net-(R13-P$1)") (class "Default")
      (node (ref "LED5") (pin "C") (pinfunction "C_C") (pintype "passive"))
      (node (ref "R13") (pin "1") (pinfunction "P$1_1") (pintype "passive"))
    )
    (net (code "45") (name "Net-(R13-P$2)") (class "Default")
      (node (ref "R13") (pin "2") (pinfunction "P$2_2") (pintype "passive"))
      (node (ref "U4") (pin "21") (pinfunction "LED_UART_21") (pintype "bidirectional"))
    )
    (net (code "46") (name "Net-(R17-P$2)") (class "Default")
      (node (ref "R17") (pin "2") (pinfunction "P$2_2") (pintype "passive"))
      (node (ref "SW3") (pin "6") (pinfunction "6_6") (pintype "bidirectional"))
    )
    (net (code "47") (name "Net-(R18-P$2)") (class "Default")
      (node (ref "R18") (pin "2") (pinfunction "P$2_2") (pintype "passive"))
      (node (ref "SW3") (pin "2") (pinfunction "2_2") (pintype "bidirectional"))
    )
    (net (code "48") (name "Net-(RESET-S)") (class "Default")
      (node (ref "D6") (pin "K") (pinfunction "K_K") (pintype "passive"))
      (node (ref "RESET") (pin "P$2") (pinfunction "S_P$2") (pintype "passive"))
      (node (ref "U4") (pin "1") (pinfunction "NRESET_FB_BL_1") (pintype "bidirectional"))
      (node (ref "U4") (pin "3") (pinfunction "NRESET_FB_ISP_3") (pintype "bidirectional"))
    )
    (net (code "49") (name "Net-(T1-G)") (class "Default")
      (node (ref "T1") (pin "1") (pinfunction "G_1") (pintype "passive"))
      (node (ref "U4") (pin "15") (pinfunction "USB_SCON_15") (pintype "bidirectional"))
    )
    (net (code "50") (name "P5V-VIN") (class "Default")
      (node (ref "BRD1") (pin "8") (pinfunction "VIN_8") (pintype "bidirectional"))
      (node (ref "D4") (pin "A") (pinfunction "A_A") (pintype "passive"))
    )
    (net (code "51") (name "P5V_USB") (class "Default")
      (node (ref "C16") (pin "1") (pinfunction "P$1_1") (pintype "passive"))
      (node (ref "CON1") (pin "VBUS") (pinfunction "VBUS_VBUS") (pintype "bidirectional"))
      (node (ref "D1") (pin "A") (pinfunction "A_A") (pintype "passive"))
      (node (ref "D3") (pin "A") (pinfunction "A_A") (pintype "passive"))
    )
    (net (code "52") (name "RFU1") (class "Default")
      (node (ref "U1") (pin "P$2") (pinfunction "RFU1_P$2") (pintype "bidirectional"))
    )
    (net (code "53") (name "RFU2") (class "Default")
      (node (ref "R6") (pin "2") (pinfunction "P$2_2") (pintype "passive"))
      (node (ref "U1") (pin "P$6") (pinfunction "RFU2_P$6") (pintype "bidirectional"))
    )
    (net (code "54") (name "RFU3") (class "Default")
      (node (ref "U1") (pin "P$7") (pinfunction "RFU3_P$7") (pintype "bidirectional"))
    )
    (net (code "55") (name "RFU4") (class "Default")
      (node (ref "U1") (pin "P$8") (pinfunction "RFU4_P$8") (pintype "bidirectional"))
    )
    (net (code "56") (name "RFU5") (class "Default")
      (node (ref "U1") (pin "P$18") (pinfunction "RFU5_P$18") (pintype "bidirectional"))
    )
    (net (code "57") (name "RFU6") (class "Default")
      (node (ref "U1") (pin "P$19") (pinfunction "RFU6_P$19") (pintype "bidirectional"))
    )
    (net (code "58") (name "RFU7") (class "Default")
      (node (ref "U1") (pin "P$21") (pinfunction "RFU7_P$21") (pintype "bidirectional"))
    )
    (net (code "59") (name "RFU8") (class "Default")
      (node (ref "U1") (pin "P$22") (pinfunction "RFU8_P$22") (pintype "bidirectional"))
    )
    (net (code "60") (name "SPI_MISO") (class "Default")
      (node (ref "R23") (pin "2") (pinfunction "P$2_2") (pintype "passive"))
      (node (ref "U1") (pin "P$12") (pinfunction "SPI_MISO_P$12") (pintype "bidirectional"))
      (node (ref "U3") (pin "8") (pinfunction "SO_8") (pintype "bidirectional"))
    )
    (net (code "61") (name "SPI_MOSI") (class "Default")
      (node (ref "R22") (pin "2") (pinfunction "P$2_2") (pintype "passive"))
      (node (ref "U1") (pin "P$11") (pinfunction "SPI_MOSI_P$11") (pintype "bidirectional"))
      (node (ref "U3") (pin "1") (pinfunction "SI_1") (pintype "bidirectional"))
    )
    (net (code "62") (name "SPI_NSS") (class "Default")
      (node (ref "R21") (pin "2") (pinfunction "P$2_2") (pintype "passive"))
      (node (ref "U1") (pin "P$9") (pinfunction "SPI_NSS_P$9") (pintype "bidirectional"))
      (node (ref "U3") (pin "4") (pinfunction "~{CS}_4") (pintype "bidirectional"))
    )
    (net (code "63") (name "SPI_SCK") (class "Default")
      (node (ref "R24") (pin "2") (pinfunction "P$2_2") (pintype "passive"))
      (node (ref "U1") (pin "P$10") (pinfunction "SPI_SCK_P$10") (pintype "bidirectional"))
      (node (ref "U3") (pin "2") (pinfunction "SCK_2") (pintype "bidirectional"))
    )
    (net (code "64") (name "TGT_NRESET") (class "Default")
      (node (ref "BRD1") (pin "3") (pinfunction "NRESET_3") (pintype "bidirectional"))
      (node (ref "D6") (pin "A") (pinfunction "A_A") (pintype "passive"))
      (node (ref "U1") (pin "P$33") (pinfunction "NRESET_P$33") (pintype "bidirectional"))
      (node (ref "U4") (pin "8") (pinfunction "TGT_NRESET_8") (pintype "bidirectional"))
    )
    (net (code "65") (name "TGT_RX") (class "Default")
      (node (ref "U1") (pin "P$16") (pinfunction "UART0_RX_P$16") (pintype "bidirectional"))
      (node (ref "U4") (pin "32") (pinfunction "TGT_RX_32") (pintype "bidirectional"))
    )
    (net (code "66") (name "TGT_SWCLK") (class "Default")
      (node (ref "U1") (pin "P$29") (pinfunction "SWCLK_P$29") (pintype "bidirectional"))
      (node (ref "U4") (pin "16") (pinfunction "TGT_SWCLK_16") (pintype "bidirectional"))
    )
    (net (code "67") (name "TGT_SWDIO") (class "Default")
      (node (ref "U1") (pin "P$30") (pinfunction "SWDIO_P$30") (pintype "bidirectional"))
      (node (ref "U4") (pin "17") (pinfunction "TGT_SWDIO_17") (pintype "bidirectional"))
    )
    (net (code "68") (name "TGT_TX") (class "Default")
      (node (ref "U1") (pin "P$15") (pinfunction "UART0_TX_P$15") (pintype "bidirectional"))
      (node (ref "U4") (pin "31") (pinfunction "TGT_TX_31") (pintype "bidirectional"))
    )
    (net (code "69") (name "UART1_CTS") (class "Default")
      (node (ref "R19") (pin "2") (pinfunction "P$2_2") (pintype "passive"))
      (node (ref "U1") (pin "P$32") (pinfunction "UART1_CTS_P$32") (pintype "bidirectional"))
    )
    (net (code "70") (name "UART1_RTS") (class "Default")
      (node (ref "R20") (pin "2") (pinfunction "P$2_2") (pintype "passive"))
      (node (ref "U1") (pin "P$31") (pinfunction "UART1_RTS_P$31") (pintype "bidirectional"))
    )
    (net (code "71") (name "UART1_RX") (class "Default")
      (node (ref "SW3") (pin "3") (pinfunction "3_3") (pintype "bidirectional"))
      (node (ref "SW3") (pin "5") (pinfunction "5_5") (pintype "bidirectional"))
      (node (ref "U1") (pin "P$14") (pinfunction "UART1_RX_P$14") (pintype "bidirectional"))
    )
    (net (code "72") (name "UART1_TX") (class "Default")
      (node (ref "SW3") (pin "1") (pinfunction "1_1") (pintype "bidirectional"))
      (node (ref "SW3") (pin "7") (pinfunction "7_7") (pintype "bidirectional"))
      (node (ref "U1") (pin "P$13") (pinfunction "UART1_TX_P$13") (pintype "bidirectional"))
    )
    (net (code "73") (name "USB_D+") (class "Default")
      (node (ref "CON1") (pin "D+") (pinfunction "D+_D+") (pintype "bidirectional"))
      (node (ref "R4") (pin "1") (pinfunction "P$1_1") (pintype "passive"))
    )
    (net (code "74") (name "USB_D-") (class "Default")
      (node (ref "CON1") (pin "D-") (pinfunction "D-_D-") (pintype "bidirectional"))
      (node (ref "R7") (pin "1") (pinfunction "P$1_1") (pintype "passive"))
    )
    (net (code "75") (name "WAKE") (class "Default")
      (node (ref "R14") (pin "1") (pinfunction "P$1_1") (pintype "passive"))
      (node (ref "U1") (pin "P$34") (pinfunction "WAKE_P$34") (pintype "bidirectional"))
    )
    (net (code "76") (name "unconnected-(ANT1-2-PadP$2)") (class "Default")
      (node (ref "ANT1") (pin "P$2") (pinfunction "2_P$2") (pintype "passive"))
    )
    (net (code "77") (name "unconnected-(BRD1-A3-Pad12)") (class "Default")
      (node (ref "BRD1") (pin "12") (pinfunction "A3_12") (pintype "bidirectional"))
    )
    (net (code "78") (name "unconnected-(BRD1-A4-Pad13)") (class "Default")
      (node (ref "BRD1") (pin "13") (pinfunction "A4_13") (pintype "bidirectional"))
    )
    (net (code "79") (name "unconnected-(BRD1-A5-Pad14)") (class "Default")
      (node (ref "BRD1") (pin "14") (pinfunction "A5_14") (pintype "bidirectional"))
    )
    (net (code "80") (name "unconnected-(BRD1-AREF-Pad30)") (class "Default")
      (node (ref "BRD1") (pin "30") (pinfunction "AREF_30") (pintype "bidirectional"))
    )
    (net (code "81") (name "unconnected-(BRD1-D4-Pad19)") (class "Default")
      (node (ref "BRD1") (pin "19") (pinfunction "D4_19") (pintype "bidirectional"))
    )
    (net (code "82") (name "unconnected-(BRD1-D5-Pad20)") (class "Default")
      (node (ref "BRD1") (pin "20") (pinfunction "D5_20") (pintype "bidirectional"))
    )
    (net (code "83") (name "unconnected-(BRD1-D6-Pad21)") (class "Default")
      (node (ref "BRD1") (pin "21") (pinfunction "D6_21") (pintype "bidirectional"))
    )
    (net (code "84") (name "unconnected-(BRD1-D7-Pad22)") (class "Default")
      (node (ref "BRD1") (pin "22") (pinfunction "D7_22") (pintype "bidirectional"))
    )
    (net (code "85") (name "unconnected-(BRD1-D8-Pad23)") (class "Default")
      (node (ref "BRD1") (pin "23") (pinfunction "D8_23") (pintype "bidirectional"))
    )
    (net (code "86") (name "unconnected-(BRD1-D9-Pad24)") (class "Default")
      (node (ref "BRD1") (pin "24") (pinfunction "D9_24") (pintype "bidirectional"))
    )
    (net (code "87") (name "unconnected-(BRD1-NC-Pad1)") (class "Default")
      (node (ref "BRD1") (pin "1") (pinfunction "NC_1") (pintype "bidirectional"))
    )
    (net (code "88") (name "unconnected-(U1-ANT2-PadP$47)") (class "Default")
      (node (ref "U1") (pin "P$47") (pinfunction "ANT2_P$47") (pintype "bidirectional"))
    )
    (net (code "89") (name "unconnected-(U2-NC-Pad4)") (class "Default")
      (node (ref "U2") (pin "4") (pinfunction "NC_4") (pintype "bidirectional"))
    )
    (net (code "90") (name "unconnected-(U4-NC2-Pad10)") (class "Default")
      (node (ref "U4") (pin "10") (pinfunction "NC2_10") (pintype "bidirectional"))
    )
    (net (code "91") (name "unconnected-(U4-NC3-Pad11)") (class "Default")
      (node (ref "U4") (pin "11") (pinfunction "NC3_11") (pintype "bidirectional"))
    )
    (net (code "92") (name "unconnected-(U4-NC4-Pad19)") (class "Default")
      (node (ref "U4") (pin "19") (pinfunction "NC4_19") (pintype "bidirectional"))
    )
    (net (code "93") (name "unconnected-(U4-NC5-Pad20)") (class "Default")
      (node (ref "U4") (pin "20") (pinfunction "NC5_20") (pintype "bidirectional"))
    )
    (net (code "94") (name "unconnected-(U4-NC6-Pad22)") (class "Default")
      (node (ref "U4") (pin "22") (pinfunction "NC6_22") (pintype "bidirectional"))
    )
    (net (code "95") (name "unconnected-(U4-NC7-Pad23)") (class "Default")
      (node (ref "U4") (pin "23") (pinfunction "NC7_23") (pintype "bidirectional"))
    )
    (net (code "96") (name "unconnected-(U4-NC8-Pad24)") (class "Default")
      (node (ref "U4") (pin "24") (pinfunction "NC8_24") (pintype "bidirectional"))
    )
    (net (code "97") (name "unconnected-(U4-NC9-Pad25)") (class "Default")
      (node (ref "U4") (pin "25") (pinfunction "NC9_25") (pintype "bidirectional"))
    )
    (net (code "98") (name "unconnected-(U4-NC10-Pad28)") (class "Default")
      (node (ref "U4") (pin "28") (pinfunction "NC10_28") (pintype "bidirectional"))
    )
    (net (code "99") (name "unconnected-(U4-NC11-Pad30)") (class "Default")
      (node (ref "U4") (pin "30") (pinfunction "NC11_30") (pintype "bidirectional"))
    )
    (net (code "100") (name "unconnected-(U4-SLEEP_NREQ-Pad27)") (class "Default")
      (node (ref "U4") (pin "27") (pinfunction "SLEEP_NREQ_27") (pintype "bidirectional"))
    )
    (net (code "101") (name "unconnected-(U4-TGT_SWO-Pad18)") (class "Default")
      (node (ref "U4") (pin "18") (pinfunction "TGT_SWO_18") (pintype "bidirectional"))
    )
    (net (code "102") (name "unconnected-(U4-WAKE_NREQ-Pad26)") (class "Default")
      (node (ref "U4") (pin "26") (pinfunction "WAKE_NREQ_26") (pintype "bidirectional"))
    )
  )
)
